# navilock-gps-to-bluetooth-converter-v1_2.net
KiCad netlist of a schematic drawn in EAGLE
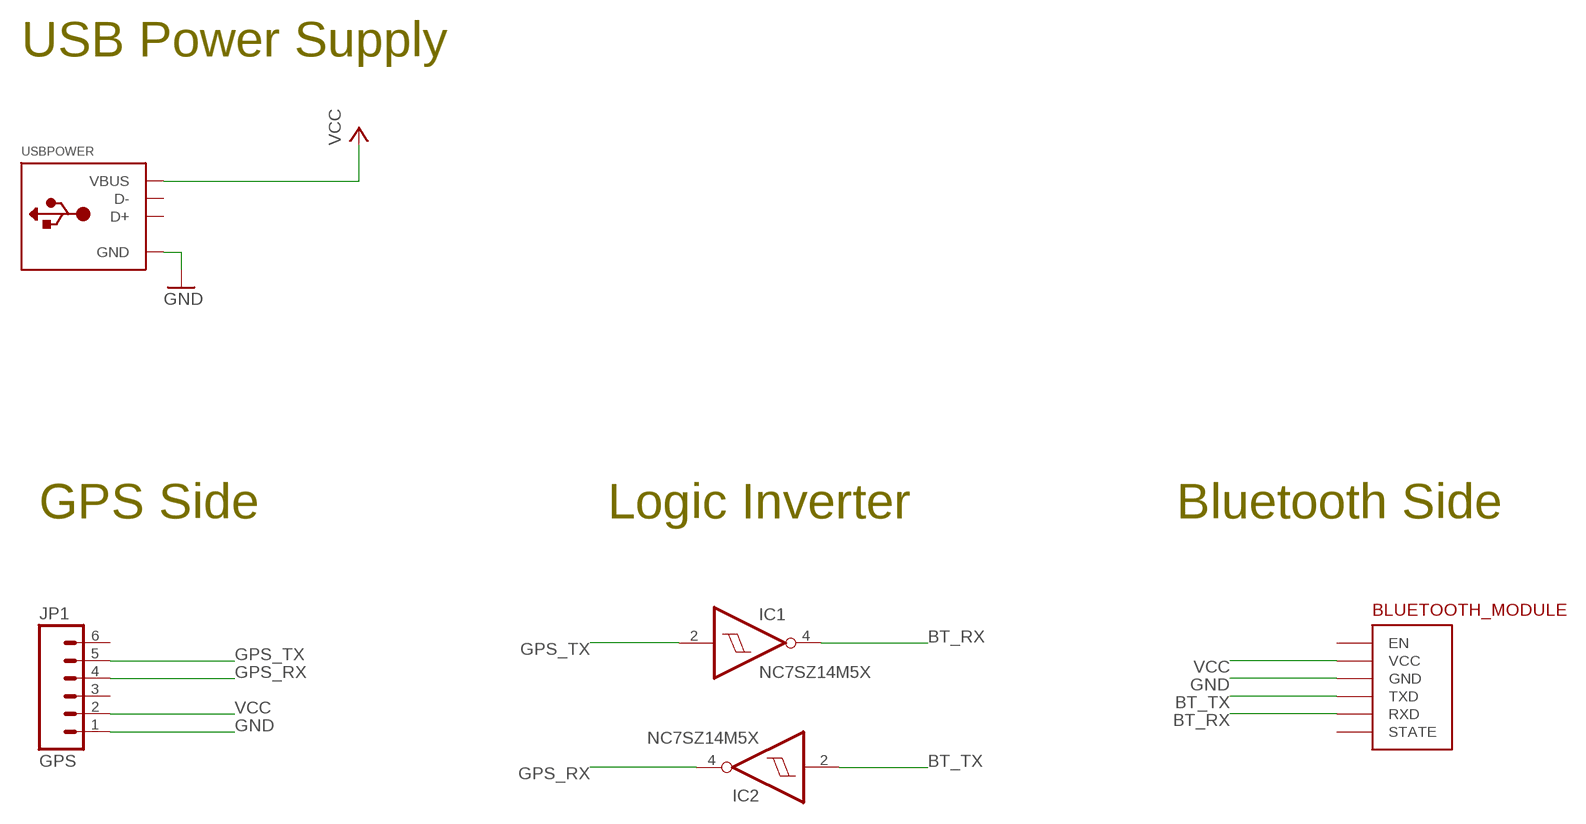
[diagram p0: schematic, sheet 1]

(export (version "E")
  (design (tool "Eeschema 10.0.6"))
  (components
    (comp (ref "BLUETOOTH_MODULE")
      (value "JY-MCU-BLUETOOTHHORIZONTAL")
      (footprint "eagle-import:JY-MCU-BLUETOOTH-HORIZONTAL")
      (libsource (lib "eagle-import") (part "JY-MCU-BLUETOOTHHORIZONTAL"))
    )
    (comp (ref "IC1")
      (value "NC7SZ14M5X")
      (footprint "eagle-import:SOT23-5")
      (libsource (lib "eagle-import") (part "NC7SZ14M5X"))
    )
    (comp (ref "IC2")
      (value "NC7SZ14M5X")
      (footprint "eagle-import:SOT23-5")
      (libsource (lib "eagle-import") (part "NC7SZ14M5X"))
    )
    (comp (ref "JP1")
      (value "GPS")
      (footprint "eagle-import:MINI-DIN6-WITH-LAT-HOLES")
      (libsource (lib "eagle-import") (part "MINI-DIN6WITH-LAT-HOLES"))
    )
    (comp (ref "USBPOWER")
      (value "USB_TYPEA")
      (footprint "eagle-import:USB_A-SMT")
      (libsource (lib "eagle-import") (part "USB_TYPEA"))
    )
  )
  (nets
    (net (code "1") (name "/BT_RX") (class "Default")
      (node (ref "BLUETOOTH_MODULE") (pin "RXD") (pinfunction "RXD_RXD") (pintype "bidirectional"))
      (node (ref "IC1") (pin "4") (pinfunction "O_4") (pintype "output"))
    )
    (net (code "2") (name "/BT_TX") (class "Default")
      (node (ref "BLUETOOTH_MODULE") (pin "TXD") (pinfunction "TXD_TXD") (pintype "bidirectional"))
      (node (ref "IC2") (pin "2") (pinfunction "I_2") (pintype "input"))
    )
    (net (code "3") (name "/GPS_RX") (class "Default")
      (node (ref "IC2") (pin "4") (pinfunction "O_4") (pintype "output"))
      (node (ref "JP1") (pin "4") (pinfunction "4_4") (pintype "passive"))
    )
    (net (code "4") (name "/GPS_TX") (class "Default")
      (node (ref "IC1") (pin "2") (pinfunction "I_2") (pintype "input"))
      (node (ref "JP1") (pin "5") (pinfunction "5_5") (pintype "passive"))
    )
    (net (code "5") (name "GND") (class "Default")
      (node (ref "BLUETOOTH_MODULE") (pin "GND") (pinfunction "GND_GND") (pintype "bidirectional"))
      (node (ref "JP1") (pin "1") (pinfunction "1_1") (pintype "passive"))
      (node (ref "USBPOWER") (pin "GND") (pinfunction "GND_GND") (pintype "power_in"))
    )
    (net (code "6") (name "VCC") (class "Default")
      (node (ref "BLUETOOTH_MODULE") (pin "VCC") (pinfunction "VCC_VCC") (pintype "bidirectional"))
      (node (ref "JP1") (pin "2") (pinfunction "2_2") (pintype "passive"))
      (node (ref "USBPOWER") (pin "VBUS") (pinfunction "VBUS_VBUS") (pintype "power_in"))
    )
    (net (code "7") (name "unconnected-(BLUETOOTH_MODULE-PadEN)") (class "Default")
      (node (ref "BLUETOOTH_MODULE") (pin "EN") (pinfunction "EN_EN") (pintype "bidirectional"))
    )
    (net (code "8") (name "unconnected-(BLUETOOTH_MODULE-PadSTATE)") (class "Default")
      (node (ref "BLUETOOTH_MODULE") (pin "STATE") (pinfunction "STATE_STATE") (pintype "bidirectional"))
    )
    (net (code "9") (name "unconnected-(JP1-Pad3)") (class "Default")
      (node (ref "JP1") (pin "3") (pinfunction "3_3") (pintype "passive"))
    )
    (net (code "10") (name "unconnected-(JP1-Pad6)") (class "Default")
      (node (ref "JP1") (pin "6") (pinfunction "6_6") (pintype "passive"))
    )
    (net (code "11") (name "unconnected-(USBPOWER-PadD+)") (class "Default")
      (node (ref "USBPOWER") (pin "D+") (pinfunction "D+_D+") (pintype "bidirectional"))
    )
    (net (code "12") (name "unconnected-(USBPOWER-PadD-)") (class "Default")
      (node (ref "USBPOWER") (pin "D-") (pinfunction "D-_D-") (pintype "bidirectional"))
    )
  )
)
